# Lora_Node_SCH.net
KiCad netlist of a schematic drawn in Altium Designer
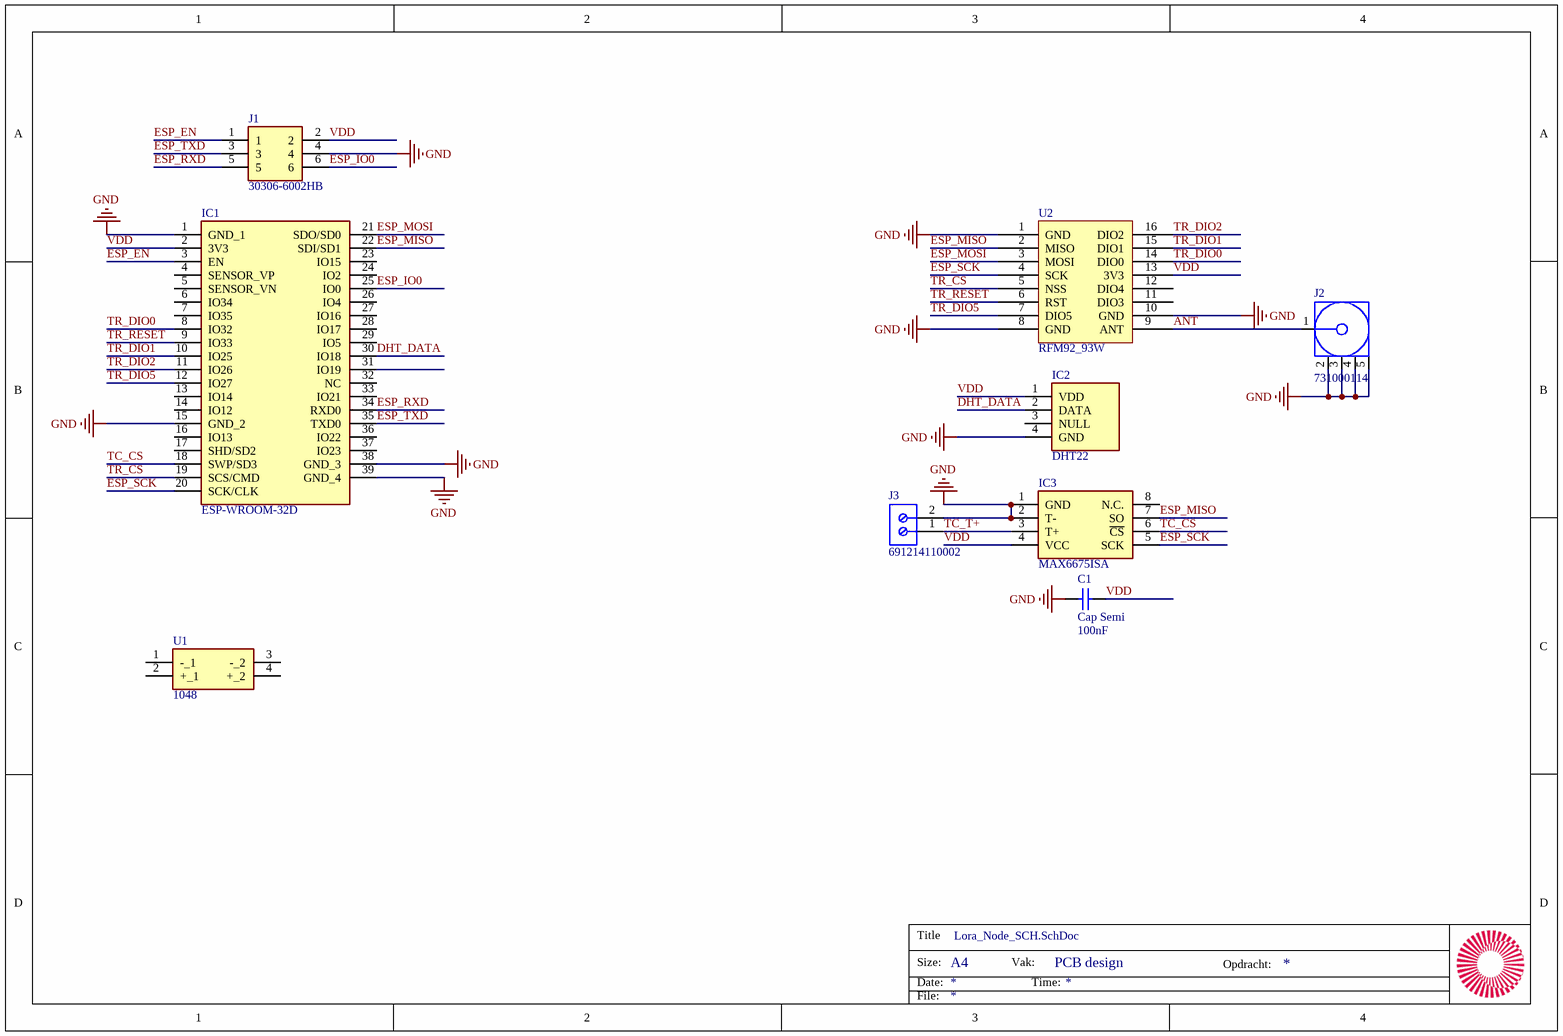
[diagram p0: Lora_Node_SCH.SchDoc]

(export (version "E")
  (design (tool "Eeschema 10.0.6"))
  (components
    (comp (ref "C1")
      (value "Cap Semi")
      (footprint "C1206")
      (description "Capacitor (Semiconductor SIM Model)")
      (fields (field (name "ALTIUM_VALUE") "100nF") (field (name "PUBLISHER") "Altium Limited"))
      (libsource (lib "Miscellaneous Devices") (part "Cap Semi"))
    )
    (comp (ref "IC1")
      (value "ESP-WROOM-32D")
      (footprint "SamacSys:ESPWROOM32D")
      (description "Integrated Circuit")
      (fields (field (name "MOUSER PART NUMBER") "356-ESP-WROOM-32D"))
      (libsource (lib "*") (part "ESP-WROOM-32D"))
    )
    (comp (ref "IC2")
      (value "DHT22")
      (footprint "SamacSys:DHT22")
      (description "Integrated Circuit")
      (libsource (lib "*") (part "DHT22"))
    )
    (comp (ref "IC3")
      (value "MAX6675ISA")
      (footprint "SamacSys:SOIC127P600X175-8N")
      (description "Integrated Circuit")
      (libsource (lib "*") (part "MAX6675ISA"))
    )
    (comp (ref "J1")
      (value "30306-6002HB")
      (footprint "SamacSys:303066002HB")
      (description "Connector")
      (fields (field (name "MOUSER PART NUMBER") "517-30306-6002HB"))
      (libsource (lib "*") (part "30306-6002HB"))
    )
    (comp (ref "J2")
      (value "731000114")
      (footprint "MOLX-731000114_V")
      (description "SMA Right-Angle PCB Jack Receptacle, Brass Body, Gold Plated, 50 Ohm, 5-Pin THD, RoHS, Tray")
      (fields (field (name "MANUFACTURER") "Molex"))
      (libsource (lib "Altium Content Vault") (part "CN-S-4F-RF5"))
    )
    (comp (ref "J3")
      (value "691214110002")
      (footprint "691214110002")
      (description "Serie 2141 - 3.50 mm Horizontal Entry Modular with Rising Cage Clamp WR-TBL, 2 pin")
      (fields (field (name "MANUFACTURER") "Wurth Elektronik") (field (name "PUBLISHER") "WurthElektronik"))
      (libsource (lib "Altium Content Vault") (part "WE-CN-1P-F-TB2"))
    )
    (comp (ref "U1")
      (value "1048")
      (footprint "SamacSys:1048")
      (description "Undefined or Miscellaneous")
      (fields (field (name "MOUSER PART NUMBER") "534-1048"))
      (libsource (lib "*") (part "1048"))
    )
    (comp (ref "U2")
      (value "RFM92_93W")
      (footprint "RFM92_93W")
      (libsource (lib "LoraNode_LIB") (part "RFM92_93W"))
    )
  )
  (nets
    (net (code "1") (name "/ANT") (class "Default")
      (node (ref "J2") (pin "1") (pinfunction "1_1") (pintype "passive"))
      (node (ref "U2") (pin "9") (pinfunction "ANT_9") (pintype "passive"))
    )
    (net (code "2") (name "/DHT_DATA") (class "Default")
      (node (ref "IC1") (pin "30") (pinfunction "IO18_30") (pintype "passive"))
      (node (ref "IC2") (pin "2") (pinfunction "DATA_2") (pintype "passive"))
    )
    (net (code "3") (name "/ESP_EN") (class "Default")
      (node (ref "IC1") (pin "3") (pinfunction "EN_3") (pintype "passive"))
      (node (ref "J1") (pin "1") (pinfunction "1_1") (pintype "passive"))
    )
    (net (code "4") (name "/ESP_IO0") (class "Default")
      (node (ref "IC1") (pin "25") (pinfunction "IO0_25") (pintype "passive"))
      (node (ref "J1") (pin "6") (pinfunction "6_6") (pintype "passive"))
    )
    (net (code "5") (name "/ESP_MISO") (class "Default")
      (node (ref "IC1") (pin "22") (pinfunction "SDI/SD1_22") (pintype "passive"))
      (node (ref "IC3") (pin "7") (pinfunction "SO_7") (pintype "passive"))
      (node (ref "U2") (pin "2") (pinfunction "MISO_2") (pintype "passive"))
    )
    (net (code "6") (name "/ESP_MOSI") (class "Default")
      (node (ref "IC1") (pin "21") (pinfunction "SDO/SD0_21") (pintype "passive"))
      (node (ref "U2") (pin "3") (pinfunction "MOSI_3") (pintype "passive"))
    )
    (net (code "7") (name "/ESP_RXD") (class "Default")
      (node (ref "IC1") (pin "34") (pinfunction "RXD0_34") (pintype "passive"))
      (node (ref "J1") (pin "5") (pinfunction "5_5") (pintype "passive"))
    )
    (net (code "8") (name "/ESP_SCK") (class "Default")
      (node (ref "IC1") (pin "20") (pinfunction "SCK/CLK_20") (pintype "passive"))
      (node (ref "IC3") (pin "5") (pinfunction "SCK_5") (pintype "passive"))
      (node (ref "U2") (pin "4") (pinfunction "SCK_4") (pintype "passive"))
    )
    (net (code "9") (name "/ESP_TXD") (class "Default")
      (node (ref "IC1") (pin "35") (pinfunction "TXD0_35") (pintype "passive"))
      (node (ref "J1") (pin "3") (pinfunction "3_3") (pintype "passive"))
    )
    (net (code "10") (name "/TC_CS") (class "Default")
      (node (ref "IC1") (pin "18") (pinfunction "SWP/SD3_18") (pintype "passive"))
      (node (ref "IC3") (pin "6") (pinfunction "~{CS}_6") (pintype "passive"))
    )
    (net (code "11") (name "/TC_T+") (class "Default")
      (node (ref "IC3") (pin "3") (pinfunction "T+_3") (pintype "passive"))
      (node (ref "J3") (pin "1") (pinfunction "1_1") (pintype "passive"))
    )
    (net (code "12") (name "/TR_CS") (class "Default")
      (node (ref "IC1") (pin "19") (pinfunction "SCS/CMD_19") (pintype "passive"))
      (node (ref "U2") (pin "5") (pinfunction "NSS_5") (pintype "passive"))
    )
    (net (code "13") (name "/TR_DIO0") (class "Default")
      (node (ref "IC1") (pin "8") (pinfunction "IO32_8") (pintype "passive"))
      (node (ref "U2") (pin "14") (pinfunction "DIO0_14") (pintype "passive"))
    )
    (net (code "14") (name "/TR_DIO1") (class "Default")
      (node (ref "IC1") (pin "10") (pinfunction "IO25_10") (pintype "passive"))
      (node (ref "U2") (pin "15") (pinfunction "DIO1_15") (pintype "passive"))
    )
    (net (code "15") (name "/TR_DIO2") (class "Default")
      (node (ref "IC1") (pin "11") (pinfunction "IO26_11") (pintype "passive"))
      (node (ref "U2") (pin "16") (pinfunction "DIO2_16") (pintype "passive"))
    )
    (net (code "16") (name "/TR_DIO5") (class "Default")
      (node (ref "IC1") (pin "12") (pinfunction "IO27_12") (pintype "passive"))
      (node (ref "U2") (pin "7") (pinfunction "DIO5_7") (pintype "passive"))
    )
    (net (code "17") (name "/TR_RESET") (class "Default")
      (node (ref "IC1") (pin "9") (pinfunction "IO33_9") (pintype "passive"))
      (node (ref "U2") (pin "6") (pinfunction "RST_6") (pintype "passive"))
    )
    (net (code "18") (name "/VDD") (class "Default")
      (node (ref "C1") (pin "2") (pinfunction "2_2") (pintype "passive"))
      (node (ref "IC1") (pin "2") (pinfunction "3V3_2") (pintype "passive"))
      (node (ref "IC2") (pin "1") (pinfunction "VDD_1") (pintype "passive"))
      (node (ref "IC3") (pin "4") (pinfunction "VCC_4") (pintype "passive"))
      (node (ref "J1") (pin "2") (pinfunction "2_2") (pintype "passive"))
      (node (ref "U2") (pin "13") (pinfunction "3V3_13") (pintype "passive"))
    )
    (net (code "19") (name "GND") (class "Default")
      (node (ref "C1") (pin "1") (pinfunction "1_1") (pintype "passive"))
      (node (ref "IC1") (pin "1") (pinfunction "GND_1_1") (pintype "passive"))
      (node (ref "IC1") (pin "15") (pinfunction "GND_2_15") (pintype "passive"))
      (node (ref "IC1") (pin "38") (pinfunction "GND_3_38") (pintype "passive"))
      (node (ref "IC1") (pin "39") (pinfunction "GND_4_39") (pintype "passive"))
      (node (ref "IC2") (pin "4") (pinfunction "GND_4") (pintype "passive"))
      (node (ref "IC3") (pin "1") (pinfunction "GND_1") (pintype "passive"))
      (node (ref "IC3") (pin "2") (pinfunction "T-_2") (pintype "passive"))
      (node (ref "J1") (pin "4") (pinfunction "4_4") (pintype "passive"))
      (node (ref "J2") (pin "2") (pinfunction "2_2") (pintype "passive"))
      (node (ref "J2") (pin "3") (pinfunction "3_3") (pintype "passive"))
      (node (ref "J2") (pin "4") (pinfunction "4_4") (pintype "passive"))
      (node (ref "J2") (pin "5") (pinfunction "5_5") (pintype "passive"))
      (node (ref "J3") (pin "2") (pinfunction "2_2") (pintype "passive"))
      (node (ref "U2") (pin "1") (pinfunction "GND_1") (pintype "passive"))
      (node (ref "U2") (pin "10") (pinfunction "GND_10") (pintype "passive"))
      (node (ref "U2") (pin "8") (pinfunction "GND_8") (pintype "passive"))
    )
    (net (code "20") (name "unconnected-(IC1-IO2-Pad24)") (class "Default")
      (node (ref "IC1") (pin "24") (pinfunction "IO2_24") (pintype "passive"))
    )
    (net (code "21") (name "unconnected-(IC1-IO4-Pad26)") (class "Default")
      (node (ref "IC1") (pin "26") (pinfunction "IO4_26") (pintype "passive"))
    )
    (net (code "22") (name "unconnected-(IC1-IO5-Pad29)") (class "Default")
      (node (ref "IC1") (pin "29") (pinfunction "IO5_29") (pintype "passive"))
    )
    (net (code "23") (name "unconnected-(IC1-IO12-Pad14)") (class "Default")
      (node (ref "IC1") (pin "14") (pinfunction "IO12_14") (pintype "passive"))
    )
    (net (code "24") (name "unconnected-(IC1-IO13-Pad16)") (class "Default")
      (node (ref "IC1") (pin "16") (pinfunction "IO13_16") (pintype "passive"))
    )
    (net (code "25") (name "unconnected-(IC1-IO14-Pad13)") (class "Default")
      (node (ref "IC1") (pin "13") (pinfunction "IO14_13") (pintype "passive"))
    )
    (net (code "26") (name "unconnected-(IC1-IO15-Pad23)") (class "Default")
      (node (ref "IC1") (pin "23") (pinfunction "IO15_23") (pintype "passive"))
    )
    (net (code "27") (name "unconnected-(IC1-IO16-Pad27)") (class "Default")
      (node (ref "IC1") (pin "27") (pinfunction "IO16_27") (pintype "passive"))
    )
    (net (code "28") (name "unconnected-(IC1-IO17-Pad28)") (class "Default")
      (node (ref "IC1") (pin "28") (pinfunction "IO17_28") (pintype "passive"))
    )
    (net (code "29") (name "unconnected-(IC1-IO19-Pad31)") (class "Default")
      (node (ref "IC1") (pin "31") (pinfunction "IO19_31") (pintype "passive"))
    )
    (net (code "30") (name "unconnected-(IC1-IO21-Pad33)") (class "Default")
      (node (ref "IC1") (pin "33") (pinfunction "IO21_33") (pintype "passive"))
    )
    (net (code "31") (name "unconnected-(IC1-IO22-Pad36)") (class "Default")
      (node (ref "IC1") (pin "36") (pinfunction "IO22_36") (pintype "passive"))
    )
    (net (code "32") (name "unconnected-(IC1-IO23-Pad37)") (class "Default")
      (node (ref "IC1") (pin "37") (pinfunction "IO23_37") (pintype "passive"))
    )
    (net (code "33") (name "unconnected-(IC1-IO34-Pad6)") (class "Default")
      (node (ref "IC1") (pin "6") (pinfunction "IO34_6") (pintype "passive"))
    )
    (net (code "34") (name "unconnected-(IC1-IO35-Pad7)") (class "Default")
      (node (ref "IC1") (pin "7") (pinfunction "IO35_7") (pintype "passive"))
    )
    (net (code "35") (name "unconnected-(IC1-NC-Pad32)") (class "Default")
      (node (ref "IC1") (pin "32") (pinfunction "NC_32") (pintype "passive"))
    )
    (net (code "36") (name "unconnected-(IC1-SENSOR_VN-Pad5)") (class "Default")
      (node (ref "IC1") (pin "5") (pinfunction "SENSOR_VN_5") (pintype "passive"))
    )
    (net (code "37") (name "unconnected-(IC1-SENSOR_VP-Pad4)") (class "Default")
      (node (ref "IC1") (pin "4") (pinfunction "SENSOR_VP_4") (pintype "passive"))
    )
    (net (code "38") (name "unconnected-(IC1-SHD{slash}SD2-Pad17)") (class "Default")
      (node (ref "IC1") (pin "17") (pinfunction "SHD/SD2_17") (pintype "passive"))
    )
    (net (code "39") (name "unconnected-(IC2-NULL-Pad3)") (class "Default")
      (node (ref "IC2") (pin "3") (pinfunction "NULL_3") (pintype "passive"))
    )
    (net (code "40") (name "unconnected-(IC3-N.C.-Pad8)") (class "Default")
      (node (ref "IC3") (pin "8") (pinfunction "N.C._8") (pintype "passive"))
    )
    (net (code "41") (name "unconnected-(U1-+_1-Pad2)") (class "Default")
      (node (ref "U1") (pin "2") (pinfunction "+_1_2") (pintype "passive"))
    )
    (net (code "42") (name "unconnected-(U1-+_2-Pad4)") (class "Default")
      (node (ref "U1") (pin "4") (pinfunction "+_2_4") (pintype "passive"))
    )
    (net (code "43") (name "unconnected-(U1--_1-Pad1)") (class "Default")
      (node (ref "U1") (pin "1") (pinfunction "-_1_1") (pintype "passive"))
    )
    (net (code "44") (name "unconnected-(U1--_2-Pad3)") (class "Default")
      (node (ref "U1") (pin "3") (pinfunction "-_2_3") (pintype "passive"))
    )
    (net (code "45") (name "unconnected-(U2-DIO3-Pad11)") (class "Default")
      (node (ref "U2") (pin "11") (pinfunction "DIO3_11") (pintype "passive"))
    )
    (net (code "46") (name "unconnected-(U2-DIO4-Pad12)") (class "Default")
      (node (ref "U2") (pin "12") (pinfunction "DIO4_12") (pintype "passive"))
    )
  )
)
